# AVR.net
KiCad netlist of a schematic drawn in Altium Designer
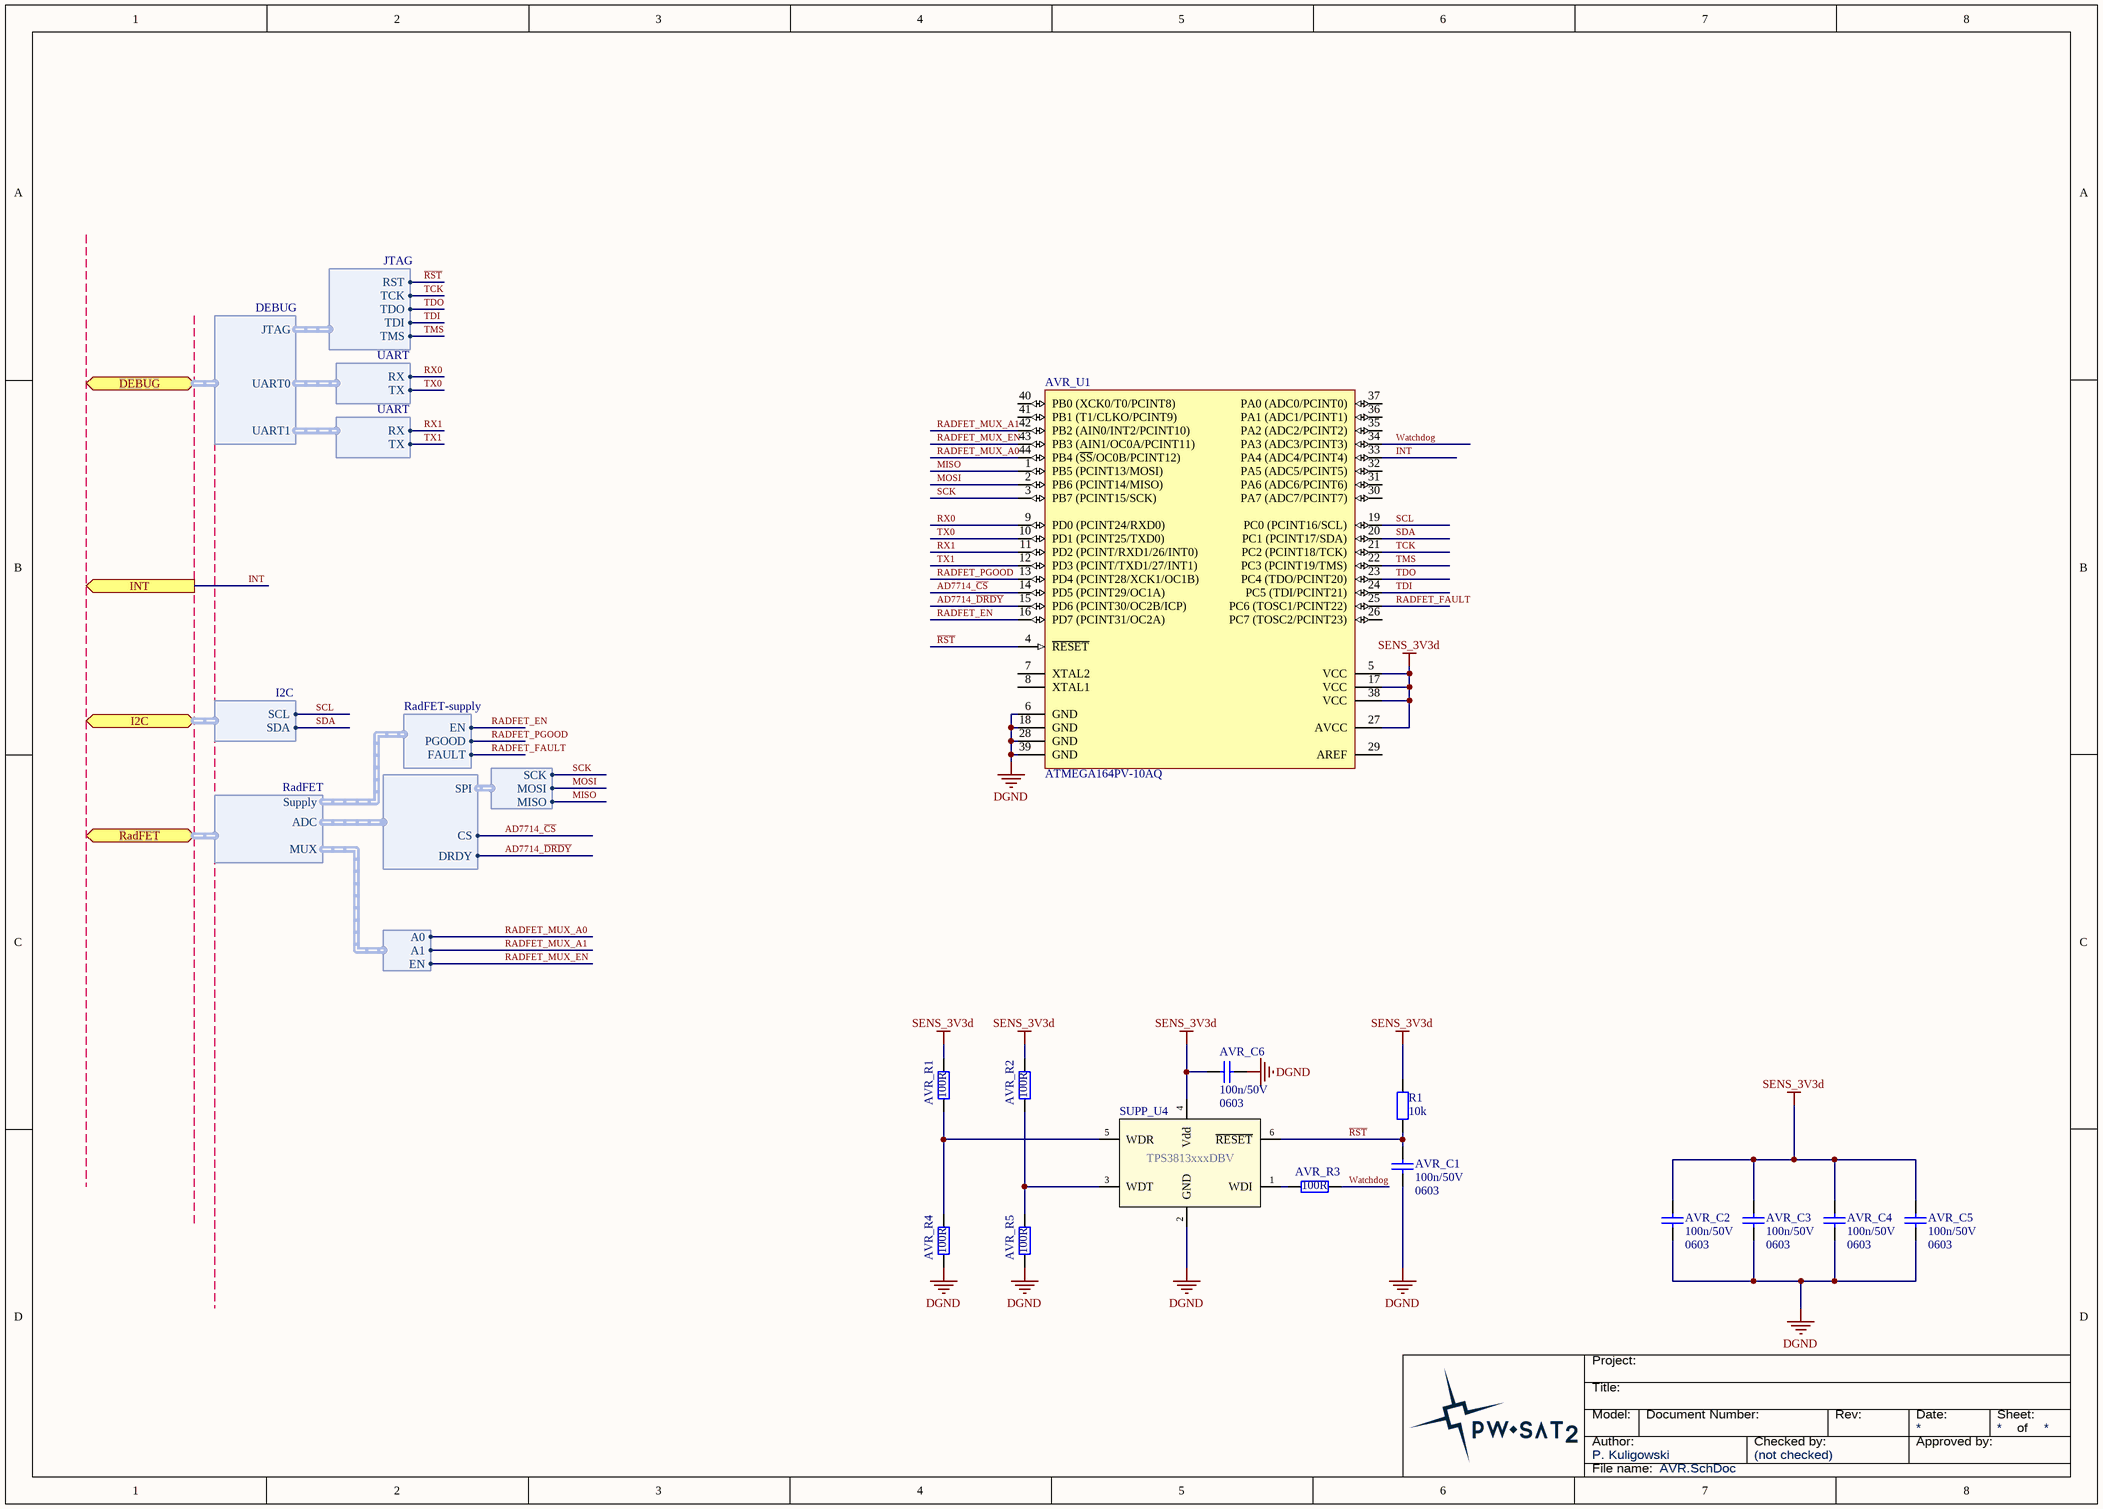
[diagram p0: AVR.SchDoc]

(export (version "E")
  (design (tool "Eeschema 10.0.6"))
  (components
    (comp (ref "AVR_C1")
      (value "100n/50V")
      (footprint "SMD_Capacitor_0603")
      (description "Ceramic Cap Kemet COTS 100n/50V X7R 0603")
      (fields
        (field (name "MANUFACTURER") "Kemet")
        (field (name "MANUFACTURERPARTNUMBER") "C0603T104K5RALTU")
        (field (name "PACKAGE") "0603")
      )
      (libsource (lib "capacitors") (part "Cer_C0603T104K5RALTU"))
    )
    (comp (ref "AVR_C2")
      (value "100n/50V")
      (footprint "SMD_Capacitor_0603")
      (description "Ceramic Cap Kemet COTS 100n/50V X7R 0603")
      (fields
        (field (name "MANUFACTURER") "Kemet")
        (field (name "MANUFACTURERPARTNUMBER") "C0603T104K5RALTU")
        (field (name "PACKAGE") "0603")
      )
      (libsource (lib "capacitors") (part "Cer_C0603T104K5RALTU"))
    )
    (comp (ref "AVR_C3")
      (value "100n/50V")
      (footprint "SMD_Capacitor_0603")
      (description "Ceramic Cap Kemet COTS 100n/50V X7R 0603")
      (fields
        (field (name "MANUFACTURER") "Kemet")
        (field (name "MANUFACTURERPARTNUMBER") "C0603T104K5RALTU")
        (field (name "PACKAGE") "0603")
      )
      (libsource (lib "capacitors") (part "Cer_C0603T104K5RALTU"))
    )
    (comp (ref "AVR_C4")
      (value "100n/50V")
      (footprint "SMD_Capacitor_0603")
      (description "Ceramic Cap Kemet COTS 100n/50V X7R 0603")
      (fields
        (field (name "MANUFACTURER") "Kemet")
        (field (name "MANUFACTURERPARTNUMBER") "C0603T104K5RALTU")
        (field (name "PACKAGE") "0603")
      )
      (libsource (lib "capacitors") (part "Cer_C0603T104K5RALTU"))
    )
    (comp (ref "AVR_C5")
      (value "100n/50V")
      (footprint "SMD_Capacitor_0603")
      (description "Ceramic Cap Kemet COTS 100n/50V X7R 0603")
      (fields
        (field (name "MANUFACTURER") "Kemet")
        (field (name "MANUFACTURERPARTNUMBER") "C0603T104K5RALTU")
        (field (name "PACKAGE") "0603")
      )
      (libsource (lib "capacitors") (part "Cer_C0603T104K5RALTU"))
    )
    (comp (ref "AVR_C6")
      (value "100n/50V")
      (footprint "SMD_Capacitor_0603")
      (description "Ceramic Cap Kemet COTS 100n/50V X7R 0603")
      (fields
        (field (name "MANUFACTURER") "Kemet")
        (field (name "MANUFACTURERPARTNUMBER") "C0603T104K5RALTU")
        (field (name "PACKAGE") "0603")
      )
      (libsource (lib "capacitors") (part "Cer_C0603T104K5RALTU"))
    )
    (comp (ref "AVR_R1") (value "100R") (footprint "SMD_Resistor_0603") (libsource (lib "") (part "Res_1")))
    (comp (ref "AVR_R2") (value "100R") (footprint "SMD_Resistor_0603") (libsource (lib "") (part "Res_1")))
    (comp (ref "AVR_R3")
      (value "100R")
      (footprint "SMD_Resistor_0603")
      (libsource (lib "resistors") (part "Res"))
    )
    (comp (ref "AVR_R4") (value "100R") (footprint "SMD_Resistor_0603") (libsource (lib "") (part "Res_1")))
    (comp (ref "AVR_R5") (value "100R") (footprint "SMD_Resistor_0603") (libsource (lib "") (part "Res_1")))
    (comp (ref "AVR_U1")
      (value "ATMEGA164PV-10AQ")
      (footprint "TQFP-44")
      (description "General-purpose microcontroller")
      (libsource (lib "microcircuits") (part "ATMEGA164PV-10AQ"))
    )
    (comp (ref "R1")
      (value "10k")
      (footprint "SMD_Resistor_0603")
      (description "10k/1% Vishay CRCW 0603 Resistor. 100mW, 100ppm, 75V.")
      (fields
        (field (name "MANUFACTURER") "Vishay")
        (field (name "MANUFACTURERPARTNUMBER") "CRCW060310K0FKxxxx")
      )
      (libsource (lib "resistors") (part "CRCW060310K0FKxxxx"))
    )
    (comp (ref "SUPP_U4")
      (value "TPS3813xxxDBV")
      (footprint "SOT23-6")
      (description "Processor Supervisory Circuits with Window-Watchdog.")
      (fields (field (name "MANUFACTURER") "Texas Instruments"))
      (libsource (lib "microcircuits") (part "TPS3813xxxDBV"))
    )
  )
  (nets
    (net (code "11") (name "/AD7714_~{CS}") (class "Default")
      (node (ref "AVR_U1") (pin "14") (pinfunction "PD5_(PCINT29/OC1A)_14") (pintype "bidirectional"))
    )
    (net (code "12") (name "/AD7714_~{DRDY}") (class "Default")
      (node (ref "AVR_U1") (pin "15") (pinfunction "PD6_(PCINT30/OC2B/ICP)_15") (pintype "bidirectional"))
    )
    (net (code "14") (name "/INT") (class "Default")
      (node (ref "AVR_U1") (pin "33") (pinfunction "PA4_(ADC4/PCINT4)_33") (pintype "bidirectional"))
    )
    (net (code "15") (name "/MISO") (class "Default")
      (node (ref "AVR_U1") (pin "1") (pinfunction "PB5_(PCINT13/MOSI)_1") (pintype "bidirectional"))
    )
    (net (code "16") (name "/MOSI") (class "Default")
      (node (ref "AVR_U1") (pin "2") (pinfunction "PB6_(PCINT14/MISO)_2") (pintype "bidirectional"))
    )
    (net (code "17") (name "/RADFET_EN") (class "Default")
      (node (ref "AVR_U1") (pin "16") (pinfunction "PD7_(PCINT31/OC2A)_16") (pintype "bidirectional"))
    )
    (net (code "18") (name "/RADFET_FAULT") (class "Default")
      (node (ref "AVR_U1") (pin "25") (pinfunction "PC6_(TOSC1/PCINT22)_25") (pintype "bidirectional"))
    )
    (net (code "19") (name "/RADFET_MUX_A0") (class "Default")
      (node (ref "AVR_U1") (pin "44") (pinfunction "PB4_(~{SS}/OC0B/PCINT12)_44") (pintype "bidirectional"))
    )
    (net (code "20") (name "/RADFET_MUX_A1") (class "Default")
      (node (ref "AVR_U1") (pin "42") (pinfunction "PB2_(AIN0/INT2/PCINT10)_42") (pintype "bidirectional"))
    )
    (net (code "21") (name "/RADFET_MUX_EN") (class "Default")
      (node (ref "AVR_U1") (pin "43") (pinfunction "PB3_(AIN1/OC0A/PCINT11)_43") (pintype "bidirectional"))
    )
    (net (code "22") (name "/RADFET_PGOOD") (class "Default")
      (node (ref "AVR_U1") (pin "13") (pinfunction "PD4_(PCINT28/XCK1/OC1B)_13") (pintype "bidirectional"))
    )
    (net (code "23") (name "/RX0") (class "Default")
      (node (ref "AVR_U1") (pin "9") (pinfunction "PD0_(PCINT24/RXD0)_9") (pintype "bidirectional"))
    )
    (net (code "24") (name "/RX1") (class "Default")
      (node (ref "AVR_U1") (pin "11") (pinfunction "PD2_(PCINT/RXD1/26/INT0)_11") (pintype "bidirectional"))
    )
    (net (code "26") (name "/SCK") (class "Default")
      (node (ref "AVR_U1") (pin "3") (pinfunction "PB7_(PCINT15/SCK)_3") (pintype "bidirectional"))
    )
    (net (code "27") (name "/SCL") (class "Default")
      (node (ref "AVR_U1") (pin "19") (pinfunction "PC0_(PCINT16/SCL)_19") (pintype "bidirectional"))
    )
    (net (code "28") (name "/SDA") (class "Default")
      (node (ref "AVR_U1") (pin "20") (pinfunction "PC1_(PCINT17/SDA)_20") (pintype "bidirectional"))
    )
    (net (code "29") (name "/TCK") (class "Default")
      (node (ref "AVR_U1") (pin "21") (pinfunction "PC2_(PCINT18/TCK)_21") (pintype "bidirectional"))
    )
    (net (code "30") (name "/TDI") (class "Default")
      (node (ref "AVR_U1") (pin "24") (pinfunction "PC5_(TDI/PCINT21)_24") (pintype "bidirectional"))
    )
    (net (code "31") (name "/TDO") (class "Default")
      (node (ref "AVR_U1") (pin "23") (pinfunction "PC4_(TDO/PCINT20)_23") (pintype "bidirectional"))
    )
    (net (code "32") (name "/TMS") (class "Default")
      (node (ref "AVR_U1") (pin "22") (pinfunction "PC3_(PCINT19/TMS)_22") (pintype "bidirectional"))
    )
    (net (code "33") (name "/TX0") (class "Default")
      (node (ref "AVR_U1") (pin "10") (pinfunction "PD1_(PCINT25/TXD0)_10") (pintype "bidirectional"))
    )
    (net (code "34") (name "/TX1") (class "Default")
      (node (ref "AVR_U1") (pin "12") (pinfunction "PD3_(PCINT/TXD1/27/INT1)_12") (pintype "bidirectional"))
    )
    (net (code "35") (name "/Watchdog") (class "Default")
      (node (ref "AVR_R3") (pin "2") (pinfunction "2_2") (pintype "passive"))
      (node (ref "AVR_U1") (pin "34") (pinfunction "PA3_(ADC3/PCINT3)_34") (pintype "bidirectional"))
    )
    (net (code "44") (name "/~{RST}") (class "Default")
      (node (ref "AVR_C1") (pin "1") (pinfunction "1_1") (pintype "passive"))
      (node (ref "AVR_U1") (pin "4") (pinfunction "~{RESET}_4") (pintype "input"))
      (node (ref "R1") (pin "2") (pinfunction "2_2") (pintype "passive"))
      (node (ref "SUPP_U4") (pin "6") (pinfunction "~{RESET}_6") (pintype "passive"))
    )
    (net (code "45") (name "DGND") (class "Default")
      (node (ref "AVR_C1") (pin "2") (pinfunction "2_2") (pintype "passive"))
      (node (ref "AVR_C2") (pin "2") (pinfunction "2_2") (pintype "passive"))
      (node (ref "AVR_C3") (pin "2") (pinfunction "2_2") (pintype "passive"))
      (node (ref "AVR_C4") (pin "2") (pinfunction "2_2") (pintype "passive"))
      (node (ref "AVR_C5") (pin "2") (pinfunction "2_2") (pintype "passive"))
      (node (ref "AVR_C6") (pin "2") (pinfunction "2_2") (pintype "passive"))
      (node (ref "AVR_R4") (pin "2") (pinfunction "2_2") (pintype "passive"))
      (node (ref "AVR_R5") (pin "2") (pinfunction "2_2") (pintype "passive"))
      (node (ref "AVR_U1") (pin "18") (pinfunction "GND_18") (pintype "power_in"))
      (node (ref "AVR_U1") (pin "28") (pinfunction "GND_28") (pintype "power_in"))
      (node (ref "AVR_U1") (pin "39") (pinfunction "GND_39") (pintype "power_in"))
      (node (ref "AVR_U1") (pin "6") (pinfunction "GND_6") (pintype "power_in"))
      (node (ref "SUPP_U4") (pin "2") (pinfunction "GND_2") (pintype "passive"))
    )
    (net (code "46") (name "Net-(SUPP_U4-WDI)") (class "Default")
      (node (ref "AVR_R3") (pin "1") (pinfunction "1_1") (pintype "passive"))
      (node (ref "SUPP_U4") (pin "1") (pinfunction "WDI_1") (pintype "passive"))
    )
    (net (code "47") (name "Net-(SUPP_U4-WDR)") (class "Default")
      (node (ref "AVR_R1") (pin "2") (pinfunction "2_2") (pintype "passive"))
      (node (ref "AVR_R4") (pin "1") (pinfunction "1_1") (pintype "passive"))
      (node (ref "SUPP_U4") (pin "5") (pinfunction "WDR_5") (pintype "passive"))
    )
    (net (code "48") (name "Net-(SUPP_U4-WDT)") (class "Default")
      (node (ref "AVR_R2") (pin "2") (pinfunction "2_2") (pintype "passive"))
      (node (ref "AVR_R5") (pin "1") (pinfunction "1_1") (pintype "passive"))
      (node (ref "SUPP_U4") (pin "3") (pinfunction "WDT_3") (pintype "passive"))
    )
    (net (code "49") (name "SENS_3V3d") (class "Default")
      (node (ref "AVR_C2") (pin "1") (pinfunction "1_1") (pintype "passive"))
      (node (ref "AVR_C3") (pin "1") (pinfunction "1_1") (pintype "passive"))
      (node (ref "AVR_C4") (pin "1") (pinfunction "1_1") (pintype "passive"))
      (node (ref "AVR_C5") (pin "1") (pinfunction "1_1") (pintype "passive"))
      (node (ref "AVR_C6") (pin "1") (pinfunction "1_1") (pintype "passive"))
      (node (ref "AVR_R1") (pin "1") (pinfunction "1_1") (pintype "passive"))
      (node (ref "AVR_R2") (pin "1") (pinfunction "1_1") (pintype "passive"))
      (node (ref "AVR_U1") (pin "17") (pinfunction "VCC_17") (pintype "power_in"))
      (node (ref "AVR_U1") (pin "27") (pinfunction "AVCC_27") (pintype "power_in"))
      (node (ref "AVR_U1") (pin "38") (pinfunction "VCC_38") (pintype "power_in"))
      (node (ref "AVR_U1") (pin "5") (pinfunction "VCC_5") (pintype "power_in"))
      (node (ref "R1") (pin "1") (pinfunction "1_1") (pintype "passive"))
      (node (ref "SUPP_U4") (pin "4") (pinfunction "Vdd_4") (pintype "passive"))
    )
    (net (code "50") (name "unconnected-(AVR_U1-AREF-Pad29)") (class "Default")
      (node (ref "AVR_U1") (pin "29") (pinfunction "AREF_29") (pintype "power_in"))
    )
    (net (code "51") (name "unconnected-(AVR_U1-PA0_(ADC0{slash}PCINT0)-Pad37)") (class "Default")
      (node (ref "AVR_U1") (pin "37") (pinfunction "PA0_(ADC0/PCINT0)_37") (pintype "bidirectional"))
    )
    (net (code "52") (name "unconnected-(AVR_U1-PA1_(ADC1{slash}PCINT1)-Pad36)") (class "Default")
      (node (ref "AVR_U1") (pin "36") (pinfunction "PA1_(ADC1/PCINT1)_36") (pintype "bidirectional"))
    )
    (net (code "53") (name "unconnected-(AVR_U1-PA2_(ADC2{slash}PCINT2)-Pad35)") (class "Default")
      (node (ref "AVR_U1") (pin "35") (pinfunction "PA2_(ADC2/PCINT2)_35") (pintype "bidirectional"))
    )
    (net (code "54") (name "unconnected-(AVR_U1-PA5_(ADC5{slash}PCINT5)-Pad32)") (class "Default")
      (node (ref "AVR_U1") (pin "32") (pinfunction "PA5_(ADC5/PCINT5)_32") (pintype "bidirectional"))
    )
    (net (code "55") (name "unconnected-(AVR_U1-PA6_(ADC6{slash}PCINT6)-Pad31)") (class "Default")
      (node (ref "AVR_U1") (pin "31") (pinfunction "PA6_(ADC6/PCINT6)_31") (pintype "bidirectional"))
    )
    (net (code "56") (name "unconnected-(AVR_U1-PA7_(ADC7{slash}PCINT7)-Pad30)") (class "Default")
      (node (ref "AVR_U1") (pin "30") (pinfunction "PA7_(ADC7/PCINT7)_30") (pintype "bidirectional"))
    )
    (net (code "57") (name "unconnected-(AVR_U1-PB0_(XCK0{slash}T0{slash}PCINT8)-Pad40)") (class "Default")
      (node (ref "AVR_U1") (pin "40") (pinfunction "PB0_(XCK0/T0/PCINT8)_40") (pintype "bidirectional"))
    )
    (net (code "58") (name "unconnected-(AVR_U1-PB1_(T1{slash}CLKO{slash}PCINT9)-Pad41)") (class "Default")
      (node (ref "AVR_U1") (pin "41") (pinfunction "PB1_(T1/CLKO/PCINT9)_41") (pintype "bidirectional"))
    )
    (net (code "59") (name "unconnected-(AVR_U1-PC7_(TOSC2{slash}PCINT23)-Pad26)") (class "Default")
      (node (ref "AVR_U1") (pin "26") (pinfunction "PC7_(TOSC2/PCINT23)_26") (pintype "bidirectional"))
    )
    (net (code "60") (name "unconnected-(AVR_U1-XTAL1-Pad8)") (class "Default")
      (node (ref "AVR_U1") (pin "8") (pinfunction "XTAL1_8") (pintype "passive"))
    )
    (net (code "61") (name "unconnected-(AVR_U1-XTAL2-Pad7)") (class "Default")
      (node (ref "AVR_U1") (pin "7") (pinfunction "XTAL2_7") (pintype "passive"))
    )
  )
)
